# ArduinoUNOSheild.net
KiCad netlist of a schematic drawn in EAGLE
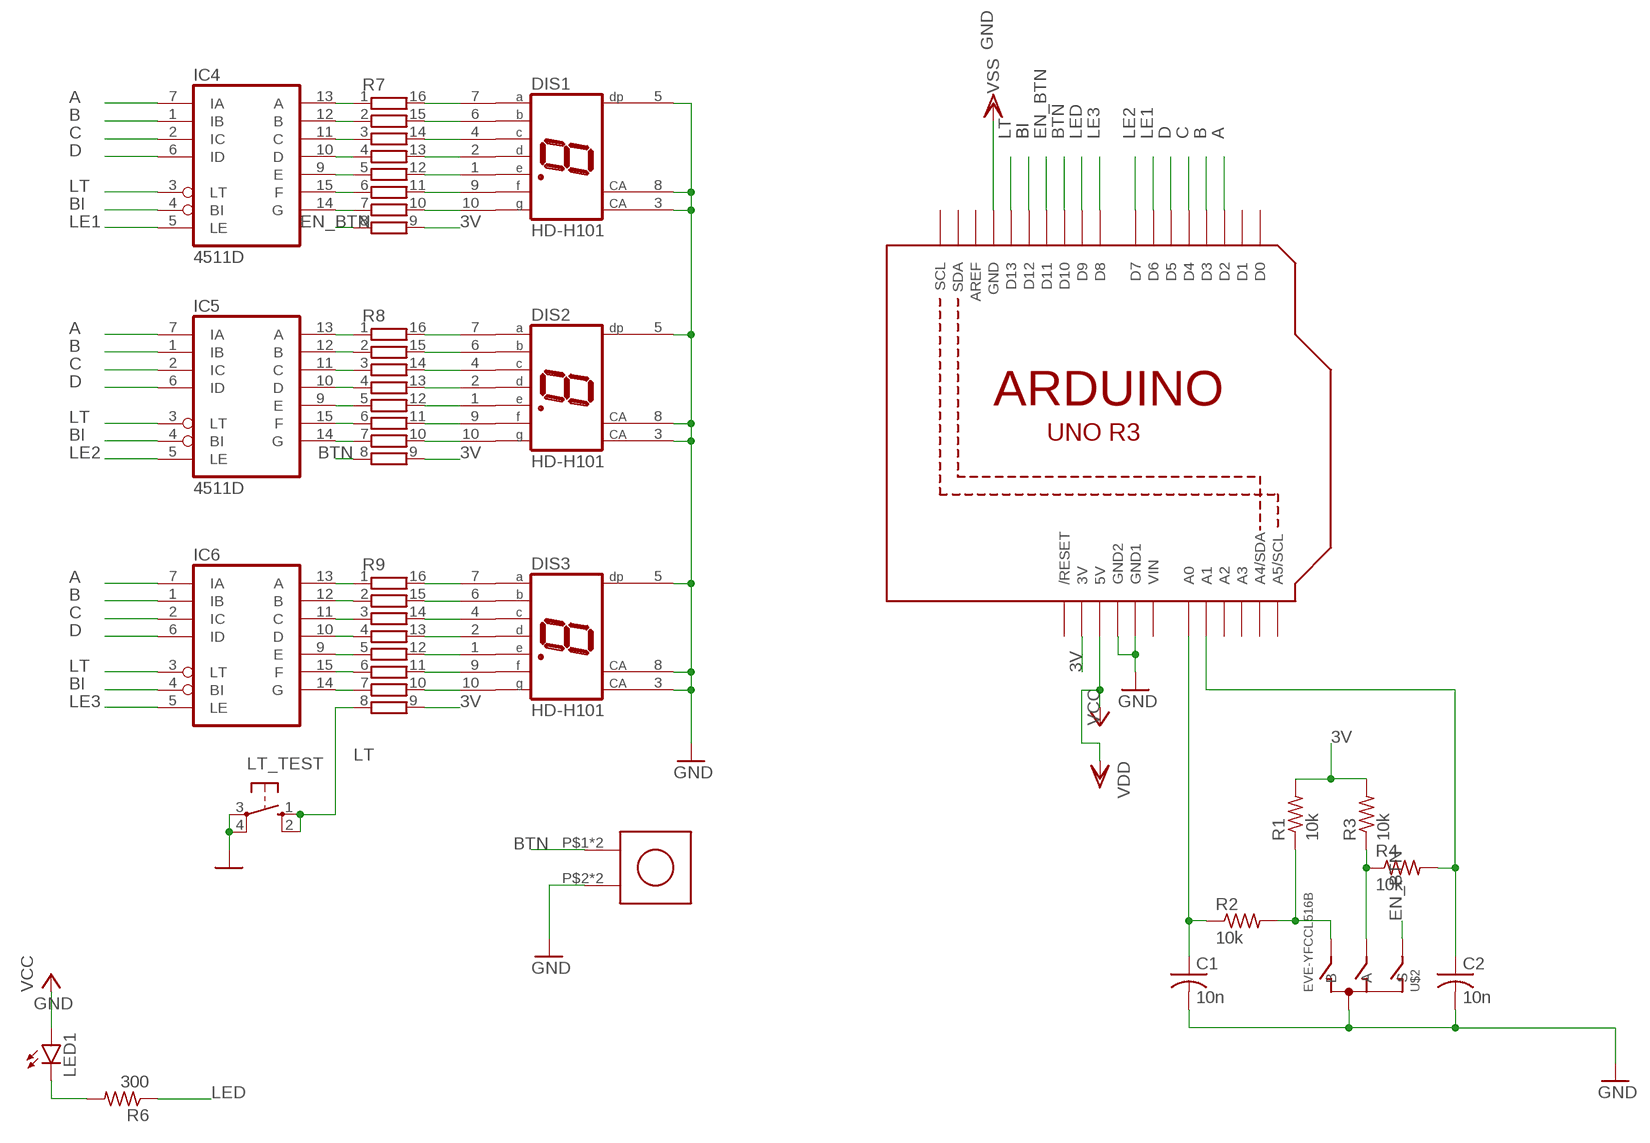
[diagram p0: schematic, sheet 1]

(export (version "E")
  (design (tool "Eeschema 10.0.6"))
  (components
    (comp (ref "C1")
      (value "10n")
      (footprint "eagle-import:C0603")
      (libsource (lib "eagle-import") (part "C-USC0603"))
    )
    (comp (ref "C2")
      (value "10n")
      (footprint "eagle-import:C0603")
      (libsource (lib "eagle-import") (part "C-USC0603"))
    )
    (comp (ref "DIS1")
      (value "HD-H101")
      (footprint "eagle-import:HDSP-M")
      (libsource (lib "eagle-import") (part "HD-H101"))
    )
    (comp (ref "DIS2")
      (value "HD-H101")
      (footprint "eagle-import:HDSP-M")
      (libsource (lib "eagle-import") (part "HD-H101"))
    )
    (comp (ref "DIS3")
      (value "HD-H101")
      (footprint "eagle-import:HDSP-M")
      (libsource (lib "eagle-import") (part "HD-H101"))
    )
    (comp (ref "IC4")
      (value "4511D")
      (footprint "eagle-import:SO16")
      (libsource (lib "eagle-import") (part "4511D"))
    )
    (comp (ref "IC5")
      (value "4511D")
      (footprint "eagle-import:SO16")
      (libsource (lib "eagle-import") (part "4511D"))
    )
    (comp (ref "IC6")
      (value "4511D")
      (footprint "eagle-import:SO16")
      (libsource (lib "eagle-import") (part "4511D"))
    )
    (comp (ref "LED1")
      (value "LEDCHIP-LED0805")
      (footprint "eagle-import:CHIP-LED0805")
      (libsource (lib "eagle-import") (part "LEDCHIP-LED0805"))
    )
    (comp (ref "LT_TEST")
      (value "10-XX")
      (footprint "eagle-import:B3F-10XX")
      (fields (field (name "MPN") "B3F-1000"))
      (libsource (lib "eagle-import") (part "10-XX"))
    )
    (comp (ref "R1")
      (value "10k")
      (footprint "eagle-import:R0603")
      (libsource (lib "eagle-import") (part "R-US_R0603"))
    )
    (comp (ref "R2")
      (value "10k")
      (footprint "eagle-import:R0603")
      (libsource (lib "eagle-import") (part "R-US_R0603"))
    )
    (comp (ref "R3")
      (value "10k")
      (footprint "eagle-import:R0603")
      (libsource (lib "eagle-import") (part "R-US_R0603"))
    )
    (comp (ref "R4")
      (value "10k")
      (footprint "eagle-import:R0603")
      (libsource (lib "eagle-import") (part "R-US_R0603"))
    )
    (comp (ref "R6")
      (value "300")
      (footprint "eagle-import:R0603")
      (libsource (lib "eagle-import") (part "R-US_R0603"))
    )
    (comp (ref "R7")
      (value "4816P-T01")
      (footprint "eagle-import:4816P")
      (fields (field (name "MF") "BOURNS, INC.") (field (name "MPN") "4816P-T01-684LF"))
      (libsource (lib "eagle-import") (part "4816P-T01"))
    )
    (comp (ref "R8")
      (value "4816P-T01")
      (footprint "eagle-import:4816P")
      (fields (field (name "MF") "BOURNS, INC.") (field (name "MPN") "4816P-T01-684LF"))
      (libsource (lib "eagle-import") (part "4816P-T01"))
    )
    (comp (ref "R9")
      (value "4816P-T01")
      (footprint "eagle-import:4816P")
      (fields (field (name "MF") "BOURNS, INC.") (field (name "MPN") "4816P-T01-684LF"))
      (libsource (lib "eagle-import") (part "4816P-T01"))
    )
    (comp (ref "U$1")
      (value "AE1027")
      (footprint "eagle-import:BUTTON5X13MM")
      (libsource (lib "eagle-import") (part "AE1027"))
    )
    (comp (ref "U$2")
      (value "EVE-YFCCL516B")
      (footprint "eagle-import:PANASONIC_EVE_Y")
      (libsource (lib "eagle-import") (part "EVE-YFCCL516B"))
    )
    (comp (ref "U1")
      (value "ARDUINOR3-NOIOREF-NOTEXT")
      (footprint "eagle-import:ARDUINOR3-NOTEXT-NOIOREF")
      (libsource (lib "eagle-import") (part "ARDUINOR3-NOIOREF-NOTEXT"))
    )
  )
  (nets
    (net (code "1") (name "+5V") (class "Default")
      (node (ref "LED1") (pin "A") (pinfunction "A_A") (pintype "passive"))
      (node (ref "U1") (pin "5V") (pinfunction "5V_5V") (pintype "power_in"))
    )
    (net (code "2") (name "/3V") (class "Default")
      (node (ref "R1") (pin "2") (pinfunction "2_2") (pintype "passive"))
      (node (ref "R3") (pin "2") (pinfunction "2_2") (pintype "passive"))
      (node (ref "R7") (pin "9") (pinfunction "9_9") (pintype "passive"))
      (node (ref "R8") (pin "9") (pinfunction "9_9") (pintype "passive"))
      (node (ref "R9") (pin "9") (pinfunction "9_9") (pintype "passive"))
      (node (ref "U1") (pin "3V") (pinfunction "3V_3V") (pintype "power_in"))
    )
    (net (code "3") (name "/A") (class "Default")
      (node (ref "IC4") (pin "7") (pinfunction "IA_7") (pintype "input"))
      (node (ref "IC5") (pin "7") (pinfunction "IA_7") (pintype "input"))
      (node (ref "IC6") (pin "7") (pinfunction "IA_7") (pintype "input"))
      (node (ref "U1") (pin "D2") (pinfunction "D2_D2") (pintype "bidirectional"))
    )
    (net (code "4") (name "/B") (class "Default")
      (node (ref "IC4") (pin "1") (pinfunction "IB_1") (pintype "input"))
      (node (ref "IC5") (pin "1") (pinfunction "IB_1") (pintype "input"))
      (node (ref "IC6") (pin "1") (pinfunction "IB_1") (pintype "input"))
      (node (ref "U1") (pin "D3") (pinfunction "D3_D3") (pintype "bidirectional"))
    )
    (net (code "5") (name "/BI") (class "Default")
      (node (ref "IC4") (pin "4") (pinfunction "BI_4") (pintype "input"))
      (node (ref "IC5") (pin "4") (pinfunction "BI_4") (pintype "input"))
      (node (ref "IC6") (pin "4") (pinfunction "BI_4") (pintype "input"))
      (node (ref "U1") (pin "D12") (pinfunction "D12_D12") (pintype "bidirectional"))
    )
    (net (code "6") (name "/BTN") (class "Default")
      (node (ref "R8") (pin "8") (pinfunction "8_8") (pintype "passive"))
      (node (ref "U$1") (pin "P$1") (pinfunction "P$1_P$1") (pintype "bidirectional"))
      (node (ref "U$1") (pin "P$11") (pinfunction "P$1_P$11") (pintype "bidirectional"))
      (node (ref "U1") (pin "D10") (pinfunction "D10_D10") (pintype "bidirectional"))
    )
    (net (code "7") (name "/C") (class "Default")
      (node (ref "IC4") (pin "2") (pinfunction "IC_2") (pintype "input"))
      (node (ref "IC5") (pin "2") (pinfunction "IC_2") (pintype "input"))
      (node (ref "IC6") (pin "2") (pinfunction "IC_2") (pintype "input"))
      (node (ref "U1") (pin "D4") (pinfunction "D4_D4") (pintype "bidirectional"))
    )
    (net (code "8") (name "/D") (class "Default")
      (node (ref "IC4") (pin "6") (pinfunction "ID_6") (pintype "input"))
      (node (ref "IC5") (pin "6") (pinfunction "ID_6") (pintype "input"))
      (node (ref "IC6") (pin "6") (pinfunction "ID_6") (pintype "input"))
      (node (ref "U1") (pin "D5") (pinfunction "D5_D5") (pintype "bidirectional"))
    )
    (net (code "9") (name "/EN_BTN") (class "Default")
      (node (ref "R7") (pin "8") (pinfunction "8_8") (pintype "passive"))
      (node (ref "U$2") (pin "S") (pinfunction "S_S") (pintype "passive"))
      (node (ref "U1") (pin "D11") (pinfunction "D11_D11") (pintype "bidirectional"))
    )
    (net (code "10") (name "/LE1") (class "Default")
      (node (ref "IC4") (pin "5") (pinfunction "LE_5") (pintype "input"))
      (node (ref "U1") (pin "D6") (pinfunction "D6_D6") (pintype "bidirectional"))
    )
    (net (code "11") (name "/LE2") (class "Default")
      (node (ref "IC5") (pin "5") (pinfunction "LE_5") (pintype "input"))
      (node (ref "U1") (pin "D7") (pinfunction "D7_D7") (pintype "bidirectional"))
    )
    (net (code "12") (name "/LE3") (class "Default")
      (node (ref "IC6") (pin "5") (pinfunction "LE_5") (pintype "input"))
      (node (ref "U1") (pin "D8") (pinfunction "D8_D8") (pintype "bidirectional"))
    )
    (net (code "13") (name "/LED") (class "Default")
      (node (ref "R6") (pin "1") (pinfunction "1_1") (pintype "passive"))
      (node (ref "U1") (pin "D9") (pinfunction "D9_D9") (pintype "bidirectional"))
    )
    (net (code "14") (name "/LT") (class "Default")
      (node (ref "IC4") (pin "3") (pinfunction "LT_3") (pintype "input"))
      (node (ref "IC5") (pin "3") (pinfunction "LT_3") (pintype "input"))
      (node (ref "IC6") (pin "3") (pinfunction "LT_3") (pintype "input"))
      (node (ref "LT_TEST") (pin "1") (pinfunction "S_1") (pintype "passive"))
      (node (ref "LT_TEST") (pin "2") (pinfunction "S1_2") (pintype "passive"))
      (node (ref "R9") (pin "8") (pinfunction "8_8") (pintype "passive"))
      (node (ref "U1") (pin "D13") (pinfunction "D13_D13") (pintype "bidirectional"))
    )
    (net (code "15") (name "/VIN") (class "Default")
      (node (ref "U1") (pin "VIN") (pinfunction "VIN_VIN") (pintype "power_in"))
    )
    (net (code "16") (name "GND") (class "Default")
      (node (ref "C1") (pin "2") (pinfunction "2_2") (pintype "passive"))
      (node (ref "C2") (pin "2") (pinfunction "2_2") (pintype "passive"))
      (node (ref "DIS1") (pin "3") (pinfunction "CA_3") (pintype "passive"))
      (node (ref "DIS1") (pin "5") (pinfunction "DP_5") (pintype "passive"))
      (node (ref "DIS1") (pin "8") (pinfunction "CA_8") (pintype "passive"))
      (node (ref "DIS2") (pin "3") (pinfunction "CA_3") (pintype "passive"))
      (node (ref "DIS2") (pin "5") (pinfunction "DP_5") (pintype "passive"))
      (node (ref "DIS2") (pin "8") (pinfunction "CA_8") (pintype "passive"))
      (node (ref "DIS3") (pin "3") (pinfunction "CA_3") (pintype "passive"))
      (node (ref "DIS3") (pin "5") (pinfunction "DP_5") (pintype "passive"))
      (node (ref "DIS3") (pin "8") (pinfunction "CA_8") (pintype "passive"))
      (node (ref "LT_TEST") (pin "3") (pinfunction "P_3") (pintype "passive"))
      (node (ref "LT_TEST") (pin "4") (pinfunction "P1_4") (pintype "passive"))
      (node (ref "U$1") (pin "P$12") (pinfunction "P$2_P$12") (pintype "bidirectional"))
      (node (ref "U$1") (pin "P$2") (pinfunction "P$2_P$2") (pintype "bidirectional"))
      (node (ref "U$2") (pin "COM") (pinfunction "C_COM") (pintype "passive"))
      (node (ref "U$2") (pin "GND") (pinfunction "C_GND") (pintype "passive"))
      (node (ref "U$2") (pin "GND1") (pinfunction "C_GND1") (pintype "passive"))
      (node (ref "U1") (pin "GND") (pinfunction "GND_GND") (pintype "power_in"))
      (node (ref "U1") (pin "GND1") (pinfunction "GND1_GND1") (pintype "power_in"))
      (node (ref "U1") (pin "GND2") (pinfunction "GND2_GND2") (pintype "power_in"))
    )
    (net (code "17") (name "Net-(C1-Pad1)") (class "Default")
      (node (ref "C1") (pin "1") (pinfunction "1_1") (pintype "passive"))
      (node (ref "R2") (pin "1") (pinfunction "1_1") (pintype "passive"))
      (node (ref "U1") (pin "A0") (pinfunction "A0_A0") (pintype "bidirectional"))
    )
    (net (code "18") (name "Net-(C2-Pad1)") (class "Default")
      (node (ref "C2") (pin "1") (pinfunction "1_1") (pintype "passive"))
      (node (ref "R4") (pin "2") (pinfunction "2_2") (pintype "passive"))
      (node (ref "U1") (pin "A1") (pinfunction "A1_A1") (pintype "bidirectional"))
    )
    (net (code "19") (name "Net-(DIS1-A)") (class "Default")
      (node (ref "DIS1") (pin "7") (pinfunction "A_7") (pintype "passive"))
      (node (ref "R7") (pin "16") (pinfunction "16_16") (pintype "passive"))
    )
    (net (code "20") (name "Net-(DIS1-B)") (class "Default")
      (node (ref "DIS1") (pin "6") (pinfunction "B_6") (pintype "passive"))
      (node (ref "R7") (pin "15") (pinfunction "15_15") (pintype "passive"))
    )
    (net (code "21") (name "Net-(DIS1-C)") (class "Default")
      (node (ref "DIS1") (pin "4") (pinfunction "C_4") (pintype "passive"))
      (node (ref "R7") (pin "14") (pinfunction "14_14") (pintype "passive"))
    )
    (net (code "22") (name "Net-(DIS1-D)") (class "Default")
      (node (ref "DIS1") (pin "2") (pinfunction "D_2") (pintype "passive"))
      (node (ref "R7") (pin "13") (pinfunction "13_13") (pintype "passive"))
    )
    (net (code "23") (name "Net-(DIS1-E)") (class "Default")
      (node (ref "DIS1") (pin "1") (pinfunction "E_1") (pintype "passive"))
      (node (ref "R7") (pin "12") (pinfunction "12_12") (pintype "passive"))
    )
    (net (code "24") (name "Net-(DIS1-F)") (class "Default")
      (node (ref "DIS1") (pin "9") (pinfunction "F_9") (pintype "passive"))
      (node (ref "R7") (pin "11") (pinfunction "11_11") (pintype "passive"))
    )
    (net (code "25") (name "Net-(DIS1-G)") (class "Default")
      (node (ref "DIS1") (pin "10") (pinfunction "G_10") (pintype "passive"))
      (node (ref "R7") (pin "10") (pinfunction "10_10") (pintype "passive"))
    )
    (net (code "26") (name "Net-(DIS2-A)") (class "Default")
      (node (ref "DIS2") (pin "7") (pinfunction "A_7") (pintype "passive"))
      (node (ref "R8") (pin "16") (pinfunction "16_16") (pintype "passive"))
    )
    (net (code "27") (name "Net-(DIS2-B)") (class "Default")
      (node (ref "DIS2") (pin "6") (pinfunction "B_6") (pintype "passive"))
      (node (ref "R8") (pin "15") (pinfunction "15_15") (pintype "passive"))
    )
    (net (code "28") (name "Net-(DIS2-C)") (class "Default")
      (node (ref "DIS2") (pin "4") (pinfunction "C_4") (pintype "passive"))
      (node (ref "R8") (pin "14") (pinfunction "14_14") (pintype "passive"))
    )
    (net (code "29") (name "Net-(DIS2-D)") (class "Default")
      (node (ref "DIS2") (pin "2") (pinfunction "D_2") (pintype "passive"))
      (node (ref "R8") (pin "13") (pinfunction "13_13") (pintype "passive"))
    )
    (net (code "30") (name "Net-(DIS2-E)") (class "Default")
      (node (ref "DIS2") (pin "1") (pinfunction "E_1") (pintype "passive"))
      (node (ref "R8") (pin "12") (pinfunction "12_12") (pintype "passive"))
    )
    (net (code "31") (name "Net-(DIS2-F)") (class "Default")
      (node (ref "DIS2") (pin "9") (pinfunction "F_9") (pintype "passive"))
      (node (ref "R8") (pin "11") (pinfunction "11_11") (pintype "passive"))
    )
    (net (code "32") (name "Net-(DIS2-G)") (class "Default")
      (node (ref "DIS2") (pin "10") (pinfunction "G_10") (pintype "passive"))
      (node (ref "R8") (pin "10") (pinfunction "10_10") (pintype "passive"))
    )
    (net (code "33") (name "Net-(DIS3-A)") (class "Default")
      (node (ref "DIS3") (pin "7") (pinfunction "A_7") (pintype "passive"))
      (node (ref "R9") (pin "16") (pinfunction "16_16") (pintype "passive"))
    )
    (net (code "34") (name "Net-(DIS3-B)") (class "Default")
      (node (ref "DIS3") (pin "6") (pinfunction "B_6") (pintype "passive"))
      (node (ref "R9") (pin "15") (pinfunction "15_15") (pintype "passive"))
    )
    (net (code "35") (name "Net-(DIS3-C)") (class "Default")
      (node (ref "DIS3") (pin "4") (pinfunction "C_4") (pintype "passive"))
      (node (ref "R9") (pin "14") (pinfunction "14_14") (pintype "passive"))
    )
    (net (code "36") (name "Net-(DIS3-D)") (class "Default")
      (node (ref "DIS3") (pin "2") (pinfunction "D_2") (pintype "passive"))
      (node (ref "R9") (pin "13") (pinfunction "13_13") (pintype "passive"))
    )
    (net (code "37") (name "Net-(DIS3-E)") (class "Default")
      (node (ref "DIS3") (pin "1") (pinfunction "E_1") (pintype "passive"))
      (node (ref "R9") (pin "12") (pinfunction "12_12") (pintype "passive"))
    )
    (net (code "38") (name "Net-(DIS3-F)") (class "Default")
      (node (ref "DIS3") (pin "9") (pinfunction "F_9") (pintype "passive"))
      (node (ref "R9") (pin "11") (pinfunction "11_11") (pintype "passive"))
    )
    (net (code "39") (name "Net-(DIS3-G)") (class "Default")
      (node (ref "DIS3") (pin "10") (pinfunction "G_10") (pintype "passive"))
      (node (ref "R9") (pin "10") (pinfunction "10_10") (pintype "passive"))
    )
    (net (code "40") (name "Net-(IC4A-A)") (class "Default")
      (node (ref "IC4") (pin "13") (pinfunction "A_13") (pintype "output"))
      (node (ref "R7") (pin "1") (pinfunction "1_1") (pintype "passive"))
    )
    (net (code "41") (name "Net-(IC4A-B)") (class "Default")
      (node (ref "IC4") (pin "12") (pinfunction "B_12") (pintype "output"))
      (node (ref "R7") (pin "2") (pinfunction "2_2") (pintype "passive"))
    )
    (net (code "42") (name "Net-(IC4A-C)") (class "Default")
      (node (ref "IC4") (pin "11") (pinfunction "C_11") (pintype "output"))
      (node (ref "R7") (pin "3") (pinfunction "3_3") (pintype "passive"))
    )
    (net (code "43") (name "Net-(IC4A-D)") (class "Default")
      (node (ref "IC4") (pin "10") (pinfunction "D_10") (pintype "output"))
      (node (ref "R7") (pin "4") (pinfunction "4_4") (pintype "passive"))
    )
    (net (code "44") (name "Net-(IC4A-E)") (class "Default")
      (node (ref "IC4") (pin "9") (pinfunction "E_9") (pintype "output"))
      (node (ref "R7") (pin "5") (pinfunction "5_5") (pintype "passive"))
    )
    (net (code "45") (name "Net-(IC4A-F)") (class "Default")
      (node (ref "IC4") (pin "15") (pinfunction "F_15") (pintype "output"))
      (node (ref "R7") (pin "6") (pinfunction "6_6") (pintype "passive"))
    )
    (net (code "46") (name "Net-(IC4A-G)") (class "Default")
      (node (ref "IC4") (pin "14") (pinfunction "G_14") (pintype "output"))
      (node (ref "R7") (pin "7") (pinfunction "7_7") (pintype "passive"))
    )
    (net (code "47") (name "Net-(IC5A-A)") (class "Default")
      (node (ref "IC5") (pin "13") (pinfunction "A_13") (pintype "output"))
      (node (ref "R8") (pin "1") (pinfunction "1_1") (pintype "passive"))
    )
    (net (code "48") (name "Net-(IC5A-B)") (class "Default")
      (node (ref "IC5") (pin "12") (pinfunction "B_12") (pintype "output"))
      (node (ref "R8") (pin "2") (pinfunction "2_2") (pintype "passive"))
    )
    (net (code "49") (name "Net-(IC5A-C)") (class "Default")
      (node (ref "IC5") (pin "11") (pinfunction "C_11") (pintype "output"))
      (node (ref "R8") (pin "3") (pinfunction "3_3") (pintype "passive"))
    )
    (net (code "50") (name "Net-(IC5A-D)") (class "Default")
      (node (ref "IC5") (pin "10") (pinfunction "D_10") (pintype "output"))
      (node (ref "R8") (pin "4") (pinfunction "4_4") (pintype "passive"))
    )
    (net (code "51") (name "Net-(IC5A-E)") (class "Default")
      (node (ref "IC5") (pin "9") (pinfunction "E_9") (pintype "output"))
      (node (ref "R8") (pin "5") (pinfunction "5_5") (pintype "passive"))
    )
    (net (code "52") (name "Net-(IC5A-F)") (class "Default")
      (node (ref "IC5") (pin "15") (pinfunction "F_15") (pintype "output"))
      (node (ref "R8") (pin "6") (pinfunction "6_6") (pintype "passive"))
    )
    (net (code "53") (name "Net-(IC5A-G)") (class "Default")
      (node (ref "IC5") (pin "14") (pinfunction "G_14") (pintype "output"))
      (node (ref "R8") (pin "7") (pinfunction "7_7") (pintype "passive"))
    )
    (net (code "54") (name "Net-(IC6A-A)") (class "Default")
      (node (ref "IC6") (pin "13") (pinfunction "A_13") (pintype "output"))
      (node (ref "R9") (pin "1") (pinfunction "1_1") (pintype "passive"))
    )
    (net (code "55") (name "Net-(IC6A-B)") (class "Default")
      (node (ref "IC6") (pin "12") (pinfunction "B_12") (pintype "output"))
      (node (ref "R9") (pin "2") (pinfunction "2_2") (pintype "passive"))
    )
    (net (code "56") (name "Net-(IC6A-C)") (class "Default")
      (node (ref "IC6") (pin "11") (pinfunction "C_11") (pintype "output"))
      (node (ref "R9") (pin "3") (pinfunction "3_3") (pintype "passive"))
    )
    (net (code "57") (name "Net-(IC6A-D)") (class "Default")
      (node (ref "IC6") (pin "10") (pinfunction "D_10") (pintype "output"))
      (node (ref "R9") (pin "4") (pinfunction "4_4") (pintype "passive"))
    )
    (net (code "58") (name "Net-(IC6A-E)") (class "Default")
      (node (ref "IC6") (pin "9") (pinfunction "E_9") (pintype "output"))
      (node (ref "R9") (pin "5") (pinfunction "5_5") (pintype "passive"))
    )
    (net (code "59") (name "Net-(IC6A-F)") (class "Default")
      (node (ref "IC6") (pin "15") (pinfunction "F_15") (pintype "output"))
      (node (ref "R9") (pin "6") (pinfunction "6_6") (pintype "passive"))
    )
    (net (code "60") (name "Net-(IC6A-G)") (class "Default")
      (node (ref "IC6") (pin "14") (pinfunction "G_14") (pintype "output"))
      (node (ref "R9") (pin "7") (pinfunction "7_7") (pintype "passive"))
    )
    (net (code "61") (name "Net-(LED1-PadC)") (class "Default")
      (node (ref "LED1") (pin "C") (pinfunction "C_C") (pintype "passive"))
      (node (ref "R6") (pin "2") (pinfunction "2_2") (pintype "passive"))
    )
    (net (code "62") (name "Net-(R1-Pad1)") (class "Default")
      (node (ref "R1") (pin "1") (pinfunction "1_1") (pintype "passive"))
      (node (ref "R2") (pin "2") (pinfunction "2_2") (pintype "passive"))
      (node (ref "U$2") (pin "B") (pinfunction "B_B") (pintype "passive"))
      (node (ref "U$2") (pin "B1") (pinfunction "B_B1") (pintype "passive"))
    )
    (net (code "63") (name "Net-(R3-Pad1)") (class "Default")
      (node (ref "R3") (pin "1") (pinfunction "1_1") (pintype "passive"))
      (node (ref "R4") (pin "1") (pinfunction "1_1") (pintype "passive"))
      (node (ref "U$2") (pin "A") (pinfunction "A_A") (pintype "passive"))
    )
    (net (code "64") (name "unconnected-(U1-A4{slash}SDA-PadA4)") (class "Default")
      (node (ref "U1") (pin "A4") (pinfunction "A4/SDA_A4") (pintype "bidirectional"))
    )
    (net (code "65") (name "unconnected-(U1-A5{slash}SCL-PadA5)") (class "Default")
      (node (ref "U1") (pin "A5") (pinfunction "A5/SCL_A5") (pintype "bidirectional"))
    )
    (net (code "66") (name "unconnected-(U1-PadA2)") (class "Default")
      (node (ref "U1") (pin "A2") (pinfunction "A2_A2") (pintype "bidirectional"))
    )
    (net (code "67") (name "unconnected-(U1-PadA3)") (class "Default")
      (node (ref "U1") (pin "A3") (pinfunction "A3_A3") (pintype "bidirectional"))
    )
    (net (code "68") (name "unconnected-(U1-PadAREF)") (class "Default")
      (node (ref "U1") (pin "AREF") (pinfunction "AREF_AREF") (pintype "bidirectional"))
    )
    (net (code "69") (name "unconnected-(U1-PadD0)") (class "Default")
      (node (ref "U1") (pin "D0") (pinfunction "D0_D0") (pintype "bidirectional"))
    )
    (net (code "70") (name "unconnected-(U1-PadD1)") (class "Default")
      (node (ref "U1") (pin "D1") (pinfunction "D1_D1") (pintype "bidirectional"))
    )
    (net (code "71") (name "unconnected-(U1-PadSCL)") (class "Default")
      (node (ref "U1") (pin "SCL") (pinfunction "SCL_SCL") (pintype "bidirectional"))
    )
    (net (code "72") (name "unconnected-(U1-PadSDA)") (class "Default")
      (node (ref "U1") (pin "SDA") (pinfunction "SDA_SDA") (pintype "bidirectional"))
    )
    (net (code "73") (name "unconnected-(U1-{slash}RESET-PadRESET)") (class "Default")
      (node (ref "U1") (pin "RESET") (pinfunction "/RESET_RESET") (pintype "bidirectional"))
    )
  )
)
